# PCB.net
KiCad netlist of a schematic drawn in Altium Designer
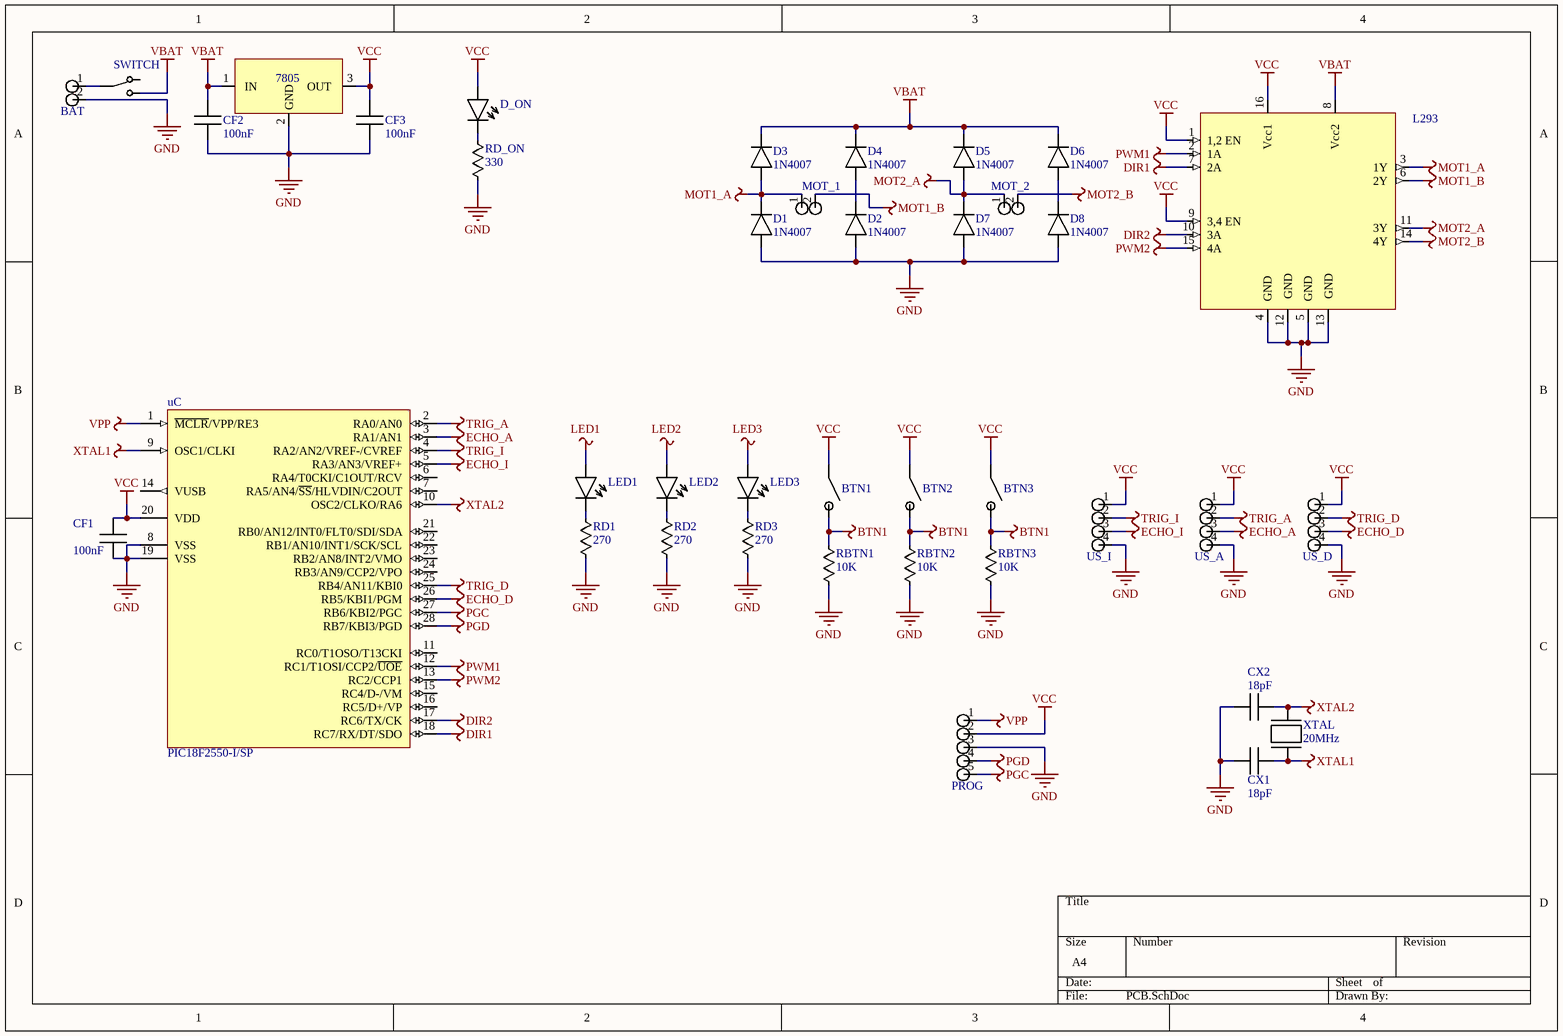
[diagram p0: PCB.SchDoc]

(export (version "E")
  (design (tool "Eeschema 10.0.6"))
  (components
    (comp (ref "7805")
      (value "LM7805")
      (footprint "TO-220-STRAIGHT")
      (libsource (lib "Components") (part "LM7805"))
    )
    (comp (ref "BAT")
      (value "HEADER-2")
      (footprint "HEADER-2-VERTICAL")
      (libsource (lib "Components") (part "HEADER-2"))
    )
    (comp (ref "BTN1")
      (value "TACT_SWITCH-SMALL-4PIN")
      (footprint "TACT_SWITCH-SMALL-4PIN")
      (libsource (lib "Components") (part "TACT_SWITCH-SMALL-4PIN"))
    )
    (comp (ref "BTN2")
      (value "TACT_SWITCH-SMALL-4PIN")
      (footprint "TACT_SWITCH-SMALL-4PIN")
      (libsource (lib "Components") (part "TACT_SWITCH-SMALL-4PIN"))
    )
    (comp (ref "BTN3")
      (value "TACT_SWITCH-SMALL-4PIN")
      (footprint "TACT_SWITCH-SMALL-4PIN")
      (libsource (lib "Components") (part "TACT_SWITCH-SMALL-4PIN"))
    )
    (comp (ref "CF1")
      (value "100nF")
      (footprint "CAP-CER")
      (fields (field (name "Comment") "CAP-CER"))
      (libsource (lib "Components") (part "CAP-CER"))
    )
    (comp (ref "CF2")
      (value "100nF")
      (footprint "CAP-CER")
      (fields (field (name "Comment") "CAP-CER"))
      (libsource (lib "Components") (part "CAP-CER"))
    )
    (comp (ref "CF3")
      (value "100nF")
      (footprint "CAP-CER")
      (fields (field (name "Comment") "CAP-CER"))
      (libsource (lib "Components") (part "CAP-CER"))
    )
    (comp (ref "CX1")
      (value "18pF")
      (footprint "CAP-CER")
      (fields (field (name "Comment") "CAP-CER"))
      (libsource (lib "Components") (part "CAP-CER"))
    )
    (comp (ref "CX2")
      (value "18pF")
      (footprint "CAP-CER")
      (fields (field (name "Comment") "CAP-CER"))
      (libsource (lib "Components") (part "CAP-CER"))
    )
    (comp (ref "D1")
      (value "DIODE")
      (footprint "DO-41")
      (fields (field (name "NAME") "1N4007"))
      (libsource (lib "Components") (part "DIODE"))
    )
    (comp (ref "D2")
      (value "DIODE")
      (footprint "DO-41")
      (fields (field (name "NAME") "1N4007"))
      (libsource (lib "Components") (part "DIODE"))
    )
    (comp (ref "D3")
      (value "DIODE")
      (footprint "DO-41")
      (fields (field (name "NAME") "1N4007"))
      (libsource (lib "Components") (part "DIODE"))
    )
    (comp (ref "D4")
      (value "DIODE")
      (footprint "DO-41")
      (fields (field (name "NAME") "1N4007"))
      (libsource (lib "Components") (part "DIODE"))
    )
    (comp (ref "D5")
      (value "DIODE")
      (footprint "DO-41")
      (fields (field (name "NAME") "1N4007"))
      (libsource (lib "Components") (part "DIODE"))
    )
    (comp (ref "D6")
      (value "DIODE")
      (footprint "DO-41")
      (fields (field (name "NAME") "1N4007"))
      (libsource (lib "Components") (part "DIODE"))
    )
    (comp (ref "D7")
      (value "DIODE")
      (footprint "DO-41")
      (fields (field (name "NAME") "1N4007"))
      (libsource (lib "Components") (part "DIODE"))
    )
    (comp (ref "D8")
      (value "DIODE")
      (footprint "DO-41")
      (fields (field (name "NAME") "1N4007"))
      (libsource (lib "Components") (part "DIODE"))
    )
    (comp (ref "D_ON") (value "LED") (footprint "LED-3MM-RED") (libsource (lib "Components") (part "LED")))
    (comp (ref "L293") (value "L293") (footprint "DIP16") (libsource (lib "Components") (part "L293")))
    (comp (ref "LED1") (value "LED") (footprint "LED-3MM-RED") (libsource (lib "Components") (part "LED")))
    (comp (ref "LED2") (value "LED") (footprint "LED-3MM-YELLOW") (libsource (lib "Components") (part "LED")))
    (comp (ref "LED3") (value "LED") (footprint "LED-3MM-GREEN") (libsource (lib "Components") (part "LED")))
    (comp (ref "MOT_1")
      (value "HEADER-2")
      (footprint "HEADER-2-VERTICAL")
      (libsource (lib "Components") (part "HEADER-2"))
    )
    (comp (ref "MOT_2")
      (value "HEADER-2")
      (footprint "HEADER-2-VERTICAL")
      (libsource (lib "Components") (part "HEADER-2"))
    )
    (comp (ref "PROG")
      (value "HEADER-5")
      (footprint "HEADER-5-VERTICAL")
      (libsource (lib "Components") (part "HEADER-5"))
    )
    (comp (ref "RBTN1")
      (value "10K")
      (footprint "RES-Axial-400mil")
      (fields (field (name "Comment") "RES"))
      (libsource (lib "Components") (part "RES"))
    )
    (comp (ref "RBTN2")
      (value "10K")
      (footprint "RES-Axial-400mil")
      (fields (field (name "Comment") "RES"))
      (libsource (lib "Components") (part "RES"))
    )
    (comp (ref "RBTN3")
      (value "10K")
      (footprint "RES-Axial-400mil")
      (fields (field (name "Comment") "RES"))
      (libsource (lib "Components") (part "RES"))
    )
    (comp (ref "RD1")
      (value "270")
      (footprint "RES-Axial-400mil")
      (fields (field (name "Comment") "RES"))
      (libsource (lib "Components") (part "RES"))
    )
    (comp (ref "RD2")
      (value "270")
      (footprint "RES-Axial-400mil")
      (fields (field (name "Comment") "RES"))
      (libsource (lib "Components") (part "RES"))
    )
    (comp (ref "RD3")
      (value "270")
      (footprint "RES-Axial-400mil")
      (fields (field (name "Comment") "RES"))
      (libsource (lib "Components") (part "RES"))
    )
    (comp (ref "RD_ON")
      (value "330")
      (footprint "RES-Axial-400mil")
      (fields (field (name "Comment") "RES"))
      (libsource (lib "Components") (part "RES"))
    )
    (comp (ref "SWITCH")
      (value "SLIDE-SWITCH")
      (footprint "SWITCH")
      (libsource (lib "Components") (part "SLIDE-SWITCH"))
    )
    (comp (ref "uC")
      (value "PIC18F2550-I/SP")
      (footprint "SPDIP300-SP28")
      (fields (field (name "PUBLISHER") "Altium Limited"))
      (libsource (lib "Microchip Microcontroller 8-Bit PIC18") (part "PIC18F2550-I/SP"))
    )
    (comp (ref "US_A")
      (value "HEADER-4")
      (footprint "HEADER-4-VERTICAL")
      (libsource (lib "Components") (part "HEADER-4"))
    )
    (comp (ref "US_D")
      (value "HEADER-4")
      (footprint "HEADER-4-VERTICAL")
      (libsource (lib "Components") (part "HEADER-4"))
    )
    (comp (ref "US_I")
      (value "HEADER-4")
      (footprint "HEADER-4-VERTICAL")
      (libsource (lib "Components") (part "HEADER-4"))
    )
    (comp (ref "XTAL")
      (value "CRYSTAL-OSC")
      (footprint "HC-49/S")
      (fields (field (name "FREQUENCY") "20MHz"))
      (libsource (lib "Components") (part "CRYSTAL-OSC"))
    )
  )
  (nets
    (net (code "1") (name "BTN1") (class "Default")
      (node (ref "BTN1") (pin "2") (pintype "passive"))
      (node (ref "BTN2") (pin "2") (pintype "passive"))
      (node (ref "BTN3") (pin "2") (pintype "passive"))
      (node (ref "RBTN1") (pin "1") (pintype "passive"))
      (node (ref "RBTN2") (pin "1") (pintype "passive"))
      (node (ref "RBTN3") (pin "1") (pintype "passive"))
    )
    (net (code "2") (name "DIR1") (class "Default")
      (node (ref "L293") (pin "7") (pinfunction "2A_7") (pintype "input"))
      (node (ref "uC") (pin "18") (pinfunction "RC7/RX/DT/SDO_18") (pintype "bidirectional"))
    )
    (net (code "3") (name "DIR2") (class "Default")
      (node (ref "L293") (pin "10") (pinfunction "3A_10") (pintype "input"))
      (node (ref "uC") (pin "17") (pinfunction "RC6/TX/CK_17") (pintype "bidirectional"))
    )
    (net (code "4") (name "ECHO_A") (class "Default")
      (node (ref "US_A") (pin "3") (pintype "passive"))
      (node (ref "uC") (pin "3") (pinfunction "RA1/AN1_3") (pintype "bidirectional"))
    )
    (net (code "5") (name "ECHO_D") (class "Default")
      (node (ref "US_D") (pin "3") (pintype "passive"))
      (node (ref "uC") (pin "26") (pinfunction "RB5/KBI1/PGM_26") (pintype "bidirectional"))
    )
    (net (code "6") (name "ECHO_I") (class "Default")
      (node (ref "US_I") (pin "3") (pintype "passive"))
      (node (ref "uC") (pin "5") (pinfunction "RA3/AN3/VREF+_5") (pintype "bidirectional"))
    )
    (net (code "7") (name "GND") (class "Default")
      (node (ref "7805") (pin "2") (pinfunction "GND_2") (pintype "power_in"))
      (node (ref "BAT") (pin "2") (pintype "passive"))
      (node (ref "CF1") (pin "1") (pintype "passive"))
      (node (ref "CF2") (pin "2") (pintype "passive"))
      (node (ref "CF3") (pin "2") (pintype "passive"))
      (node (ref "CX1") (pin "1") (pintype "passive"))
      (node (ref "CX2") (pin "1") (pintype "passive"))
      (node (ref "D1") (pin "A") (pintype "passive"))
      (node (ref "D2") (pin "A") (pintype "passive"))
      (node (ref "D7") (pin "A") (pintype "passive"))
      (node (ref "D8") (pin "A") (pintype "passive"))
      (node (ref "L293") (pin "12") (pinfunction "GND_12") (pintype "power_in"))
      (node (ref "L293") (pin "13") (pinfunction "GND_13") (pintype "power_in"))
      (node (ref "L293") (pin "4") (pinfunction "GND_4") (pintype "power_in"))
      (node (ref "L293") (pin "5") (pinfunction "GND_5") (pintype "power_in"))
      (node (ref "PROG") (pin "3") (pintype "passive"))
      (node (ref "RBTN1") (pin "2") (pintype "passive"))
      (node (ref "RBTN2") (pin "2") (pintype "passive"))
      (node (ref "RBTN3") (pin "2") (pintype "passive"))
      (node (ref "RD1") (pin "2") (pintype "passive"))
      (node (ref "RD2") (pin "2") (pintype "passive"))
      (node (ref "RD3") (pin "2") (pintype "passive"))
      (node (ref "RD_ON") (pin "2") (pintype "passive"))
      (node (ref "US_A") (pin "4") (pintype "passive"))
      (node (ref "US_D") (pin "4") (pintype "passive"))
      (node (ref "US_I") (pin "4") (pintype "passive"))
      (node (ref "uC") (pin "19") (pinfunction "VSS_19") (pintype "power_in"))
      (node (ref "uC") (pin "8") (pinfunction "VSS_8") (pintype "power_in"))
    )
    (net (code "8") (name "LED1") (class "Default") (node (ref "LED1") (pin "A") (pintype "passive")))
    (net (code "9") (name "LED2") (class "Default") (node (ref "LED2") (pin "A") (pintype "passive")))
    (net (code "10") (name "LED3") (class "Default") (node (ref "LED3") (pin "A") (pintype "passive")))
    (net (code "11") (name "MOT1_A") (class "Default")
      (node (ref "D1") (pin "K") (pintype "passive"))
      (node (ref "D3") (pin "A") (pintype "passive"))
      (node (ref "L293") (pin "3") (pinfunction "1Y_3") (pintype "output"))
      (node (ref "MOT_1") (pin "1") (pintype "passive"))
    )
    (net (code "12") (name "MOT1_B") (class "Default")
      (node (ref "L293") (pin "6") (pinfunction "2Y_6") (pintype "output"))
      (node (ref "MOT_1") (pin "2") (pintype "passive"))
    )
    (net (code "13") (name "MOT2_A") (class "Default")
      (node (ref "D5") (pin "A") (pintype "passive"))
      (node (ref "D7") (pin "K") (pintype "passive"))
      (node (ref "L293") (pin "11") (pinfunction "3Y_11") (pintype "output"))
      (node (ref "MOT_2") (pin "1") (pintype "passive"))
    )
    (net (code "14") (name "MOT2_B") (class "Default")
      (node (ref "L293") (pin "14") (pinfunction "4Y_14") (pintype "output"))
      (node (ref "MOT_2") (pin "2") (pintype "passive"))
    )
    (net (code "15") (name "Net-(BAT-Pad1)") (class "Default")
      (node (ref "BAT") (pin "1") (pintype "passive"))
      (node (ref "SWITCH") (pin "2") (pintype "power_in"))
    )
    (net (code "16") (name "Net-(D2-PadK)") (class "Default")
      (node (ref "D2") (pin "K") (pintype "passive"))
      (node (ref "D4") (pin "A") (pintype "passive"))
    )
    (net (code "17") (name "Net-(D6-PadA)") (class "Default")
      (node (ref "D6") (pin "A") (pintype "passive"))
      (node (ref "D8") (pin "K") (pintype "passive"))
    )
    (net (code "18") (name "Net-(D_ON-PadK)") (class "Default")
      (node (ref "D_ON") (pin "K") (pintype "passive"))
      (node (ref "RD_ON") (pin "1") (pintype "passive"))
    )
    (net (code "19") (name "Net-(LED1-PadK)") (class "Default")
      (node (ref "LED1") (pin "K") (pintype "passive"))
      (node (ref "RD1") (pin "1") (pintype "passive"))
    )
    (net (code "20") (name "Net-(LED2-PadK)") (class "Default")
      (node (ref "LED2") (pin "K") (pintype "passive"))
      (node (ref "RD2") (pin "1") (pintype "passive"))
    )
    (net (code "21") (name "Net-(LED3-PadK)") (class "Default")
      (node (ref "LED3") (pin "K") (pintype "passive"))
      (node (ref "RD3") (pin "1") (pintype "passive"))
    )
    (net (code "22") (name "PGC") (class "Default")
      (node (ref "PROG") (pin "5") (pintype "passive"))
      (node (ref "uC") (pin "27") (pinfunction "RB6/KBI2/PGC_27") (pintype "bidirectional"))
    )
    (net (code "23") (name "PGD") (class "Default")
      (node (ref "PROG") (pin "4") (pintype "passive"))
      (node (ref "uC") (pin "28") (pinfunction "RB7/KBI3/PGD_28") (pintype "bidirectional"))
    )
    (net (code "24") (name "PWM1") (class "Default")
      (node (ref "L293") (pin "2") (pinfunction "1A_2") (pintype "input"))
      (node (ref "uC") (pin "12") (pinfunction "RC1/T1OSI/CCP2/~{UOE}_12") (pintype "bidirectional"))
    )
    (net (code "25") (name "PWM2") (class "Default")
      (node (ref "L293") (pin "15") (pinfunction "4A_15") (pintype "input"))
      (node (ref "uC") (pin "13") (pinfunction "RC2/CCP1_13") (pintype "bidirectional"))
    )
    (net (code "26") (name "TRIG_A") (class "Default")
      (node (ref "US_A") (pin "2") (pintype "passive"))
      (node (ref "uC") (pin "2") (pinfunction "RA0/AN0_2") (pintype "bidirectional"))
    )
    (net (code "27") (name "TRIG_D") (class "Default")
      (node (ref "US_D") (pin "2") (pintype "passive"))
      (node (ref "uC") (pin "25") (pinfunction "RB4/AN11/KBI0_25") (pintype "bidirectional"))
    )
    (net (code "28") (name "TRIG_I") (class "Default")
      (node (ref "US_I") (pin "2") (pintype "passive"))
      (node (ref "uC") (pin "4") (pinfunction "RA2/AN2/VREF-/CVREF_4") (pintype "bidirectional"))
    )
    (net (code "29") (name "VBAT") (class "Default")
      (node (ref "7805") (pin "1") (pinfunction "IN_1") (pintype "power_in"))
      (node (ref "CF2") (pin "1") (pintype "passive"))
      (node (ref "D3") (pin "K") (pintype "passive"))
      (node (ref "D4") (pin "K") (pintype "passive"))
      (node (ref "D5") (pin "K") (pintype "passive"))
      (node (ref "D6") (pin "K") (pintype "passive"))
      (node (ref "L293") (pin "8") (pinfunction "Vcc2_8") (pintype "power_in"))
      (node (ref "SWITCH") (pin "3") (pintype "power_in"))
    )
    (net (code "30") (name "VCC") (class "Default")
      (node (ref "7805") (pin "3") (pinfunction "OUT_3") (pintype "power_in"))
      (node (ref "BTN1") (pin "1") (pintype "passive"))
      (node (ref "BTN2") (pin "1") (pintype "passive"))
      (node (ref "BTN3") (pin "1") (pintype "passive"))
      (node (ref "CF1") (pin "2") (pintype "passive"))
      (node (ref "CF3") (pin "1") (pintype "passive"))
      (node (ref "D_ON") (pin "A") (pintype "passive"))
      (node (ref "L293") (pin "1") (pinfunction "1,2_EN_1") (pintype "input"))
      (node (ref "L293") (pin "16") (pinfunction "Vcc1_16") (pintype "power_in"))
      (node (ref "L293") (pin "9") (pinfunction "3,4_EN_9") (pintype "input"))
      (node (ref "PROG") (pin "2") (pintype "passive"))
      (node (ref "US_A") (pin "1") (pintype "passive"))
      (node (ref "US_D") (pin "1") (pintype "passive"))
      (node (ref "US_I") (pin "1") (pintype "passive"))
      (node (ref "uC") (pin "20") (pinfunction "VDD_20") (pintype "power_in"))
    )
    (net (code "31") (name "VPP") (class "Default")
      (node (ref "PROG") (pin "1") (pintype "passive"))
      (node (ref "uC") (pin "1") (pinfunction "~{MCLR}/VPP/RE3_1") (pintype "input"))
    )
    (net (code "32") (name "XTAL1") (class "Default")
      (node (ref "CX1") (pin "2") (pintype "passive"))
      (node (ref "XTAL") (pin "1") (pintype "passive"))
      (node (ref "uC") (pin "9") (pinfunction "OSC1/CLKI_9") (pintype "input"))
    )
    (net (code "33") (name "XTAL2") (class "Default")
      (node (ref "CX2") (pin "2") (pintype "passive"))
      (node (ref "XTAL") (pin "2") (pintype "passive"))
      (node (ref "uC") (pin "10") (pinfunction "OSC2/CLKO/RA6_10") (pintype "bidirectional"))
    )
    (net (code "34") (name "unconnected-(SWITCH-Pad1)") (class "Default")
      (node (ref "SWITCH") (pin "1") (pintype "power_in"))
    )
    (net (code "35") (name "unconnected-(uC-RA4{slash}T0CKI{slash}C1OUT{slash}RCV-Pad6)") (class "Default")
      (node (ref "uC") (pin "6") (pinfunction "RA4/T0CKI/C1OUT/RCV_6") (pintype "bidirectional"))
    )
    (net (code "36") (name "unconnected-(uC-RA5{slash}AN4{slash}~{SS}{slash}HLVDIN{slash}C2OUT-Pad7)") (class "Default")
      (node (ref "uC") (pin "7") (pinfunction "RA5/AN4/~{SS}/HLVDIN/C2OUT_7") (pintype "bidirectional"))
    )
    (net (code "37") (name "unconnected-(uC-RB0{slash}AN12{slash}INT0{slash}FLT0{slash}SDI{slash}SDA-Pad21)") (class "Default")
      (node (ref "uC") (pin "21") (pinfunction "RB0/AN12/INT0/FLT0/SDI/SDA_21") (pintype "bidirectional"))
    )
    (net (code "38") (name "unconnected-(uC-RB1{slash}AN10{slash}INT1{slash}SCK{slash}SCL-Pad22)") (class "Default")
      (node (ref "uC") (pin "22") (pinfunction "RB1/AN10/INT1/SCK/SCL_22") (pintype "bidirectional"))
    )
    (net (code "39") (name "unconnected-(uC-RB2{slash}AN8{slash}INT2{slash}VMO-Pad23)") (class "Default")
      (node (ref "uC") (pin "23") (pinfunction "RB2/AN8/INT2/VMO_23") (pintype "bidirectional"))
    )
    (net (code "40") (name "unconnected-(uC-RB3{slash}AN9{slash}CCP2{slash}VPO-Pad24)") (class "Default")
      (node (ref "uC") (pin "24") (pinfunction "RB3/AN9/CCP2/VPO_24") (pintype "bidirectional"))
    )
    (net (code "41") (name "unconnected-(uC-RC0{slash}T1OSO{slash}T13CKI-Pad11)") (class "Default")
      (node (ref "uC") (pin "11") (pinfunction "RC0/T1OSO/T13CKI_11") (pintype "bidirectional"))
    )
    (net (code "42") (name "unconnected-(uC-RC4{slash}D-{slash}VM-Pad15)") (class "Default")
      (node (ref "uC") (pin "15") (pinfunction "RC4/D-/VM_15") (pintype "bidirectional"))
    )
    (net (code "43") (name "unconnected-(uC-RC5{slash}D+{slash}VP-Pad16)") (class "Default")
      (node (ref "uC") (pin "16") (pinfunction "RC5/D+/VP_16") (pintype "bidirectional"))
    )
    (net (code "44") (name "unconnected-(uC-VUSB-Pad14)") (class "Default")
      (node (ref "uC") (pin "14") (pinfunction "VUSB_14") (pintype "output"))
    )
  )
)
